# DEVICE2.net
KiCad netlist of a schematic drawn in Altium Designer
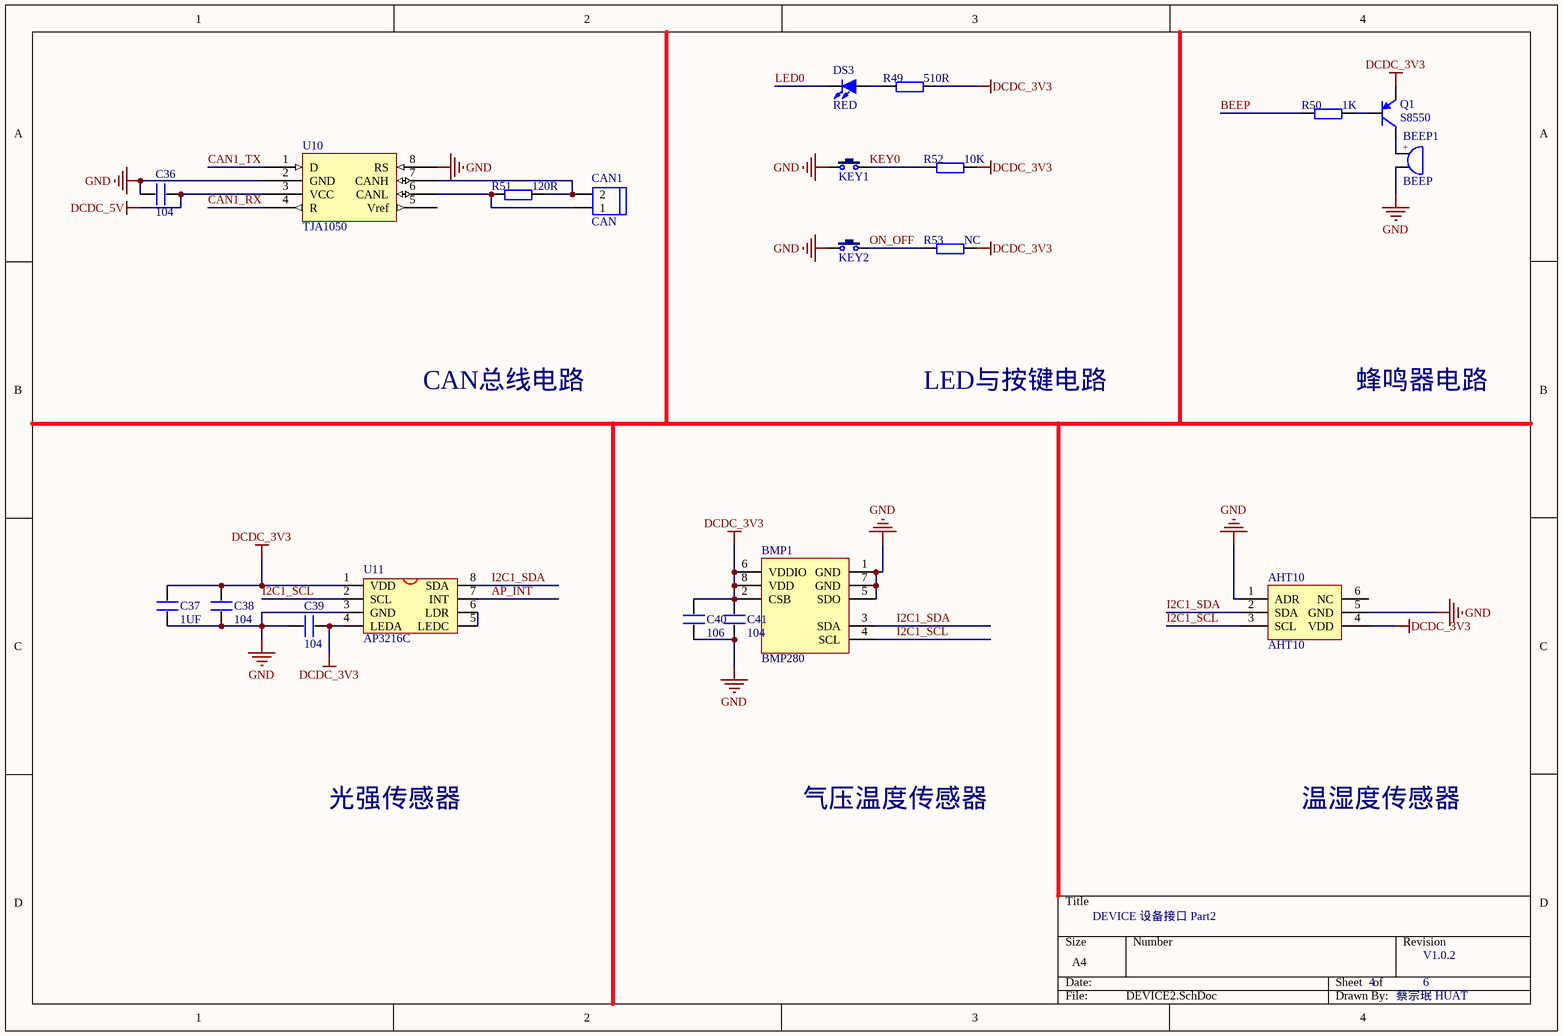
[diagram p0: DEVICE2.SchDoc]

(export (version "E")
  (design (tool "Eeschema 10.0.6"))
  (components
    (comp (ref "AHT10")
      (value "AHT10")
      (footprint "AHT10 温湿度传感器")
      (libsource (lib "ZZW封装汇总") (part "AHT10 温湿度传感器"))
    )
    (comp (ref "BEEP1")
      (value "BEEP")
      (footprint "BEEP 5x9x5.5")
      (description "蜂鸣器")
      (fields (field (name "版权归属") "源创客"))
      (libsource (lib "IMX6UL_ALPHA(底板)_V2.0") (part "BEEP"))
    )
    (comp (ref "BMP1") (value "BMP280") (footprint "BMP280") (libsource (lib "ZZW封装汇总") (part "BMP280")))
    (comp (ref "C36") (value "104") (footprint "C_0603P") (libsource (lib "ZZW封装汇总") (part "C")))
    (comp (ref "C37") (value "1UF") (footprint "C_0603P") (libsource (lib "ZZW封装汇总") (part "C")))
    (comp (ref "C38") (value "104") (footprint "C_0603P") (libsource (lib "ZZW封装汇总") (part "C")))
    (comp (ref "C39") (value "104") (footprint "C_0603P") (libsource (lib "ZZW封装汇总") (part "C")))
    (comp (ref "C40") (value "106") (footprint "C_0603P") (libsource (lib "ZZW封装汇总") (part "C")))
    (comp (ref "C41") (value "104") (footprint "C_0603P") (libsource (lib "ZZW封装汇总") (part "C")))
    (comp (ref "CAN1")
      (value "CAN")
      (footprint "KF301-2P")
      (libsource (lib "IMX6UL_ALPHA(底板)_V2.0") (part "HEAD2"))
    )
    (comp (ref "DS3")
      (value "RED")
      (footprint "LED 0805R")
      (description "贴片LED")
      (fields (field (name "版权归属") "源创客"))
      (libsource (lib "IMX6UL_ALPHA(底板)_V2.0") (part "LED-SMD"))
    )
    (comp (ref "KEY1")
      (value "KEY")
      (footprint "TSW DIP-6*6*5 - 2")
      (description "按键")
      (fields (field (name "版权归属") "源创客"))
      (libsource (lib "IMX6UL_ALPHA(底板)_V2.0") (part "KEY"))
    )
    (comp (ref "KEY2")
      (value "KEY")
      (footprint "TSW DIP-6*6*5 - 2")
      (description "按键")
      (fields (field (name "版权归属") "源创客"))
      (libsource (lib "IMX6UL_ALPHA(底板)_V2.0") (part "KEY"))
    )
    (comp (ref "Q1")
      (value "S8550")
      (footprint "SOT23-3L")
      (description "高频放大-PNP型")
      (fields (field (name "版权归属") "源创客"))
      (libsource (lib "IMX6UL_ALPHA(底板)_V2.0") (part "8550-SMD"))
    )
    (comp (ref "R49") (value "510R") (footprint "R_0603P") (libsource (lib "ZZW封装汇总") (part "R")))
    (comp (ref "R50") (value "1K") (footprint "R_0603P") (libsource (lib "ZZW封装汇总") (part "R")))
    (comp (ref "R51") (value "120R") (footprint "R_0603P") (libsource (lib "ZZW封装汇总") (part "R")))
    (comp (ref "R52") (value "10K") (footprint "R_0603P") (libsource (lib "ZZW封装汇总") (part "R")))
    (comp (ref "R53") (value "NC") (footprint "R_0603P") (libsource (lib "ZZW封装汇总") (part "R")))
    (comp (ref "U10")
      (value "TJA1050")
      (footprint "SOP8_N")
      (libsource (lib "IMX6UL_ALPHA(底板)_V2.0") (part "SN65HVD230D"))
    )
    (comp (ref "U11")
      (value "AP3216C")
      (footprint "QFN8")
      (description "ALS+PS Sensor")
      (libsource (lib "IMX6UL_ALPHA(底板)_V2.0") (part "AP3216C"))
    )
  )
  (nets
    (net (code "1") (name "/AP_INT") (class "Default")
      (node (ref "U11") (pin "7") (pinfunction "INT_7") (pintype "passive"))
    )
    (net (code "2") (name "/BEEP") (class "Default") (node (ref "R50") (pin "1") (pintype "passive")))
    (net (code "3") (name "/CAN1_RX") (class "Default")
      (node (ref "U10") (pin "4") (pinfunction "R_4") (pintype "output"))
    )
    (net (code "4") (name "/CAN1_TX") (class "Default")
      (node (ref "U10") (pin "1") (pinfunction "D_1") (pintype "input"))
    )
    (net (code "5") (name "/I2C1_SCL") (class "Default")
      (node (ref "AHT10") (pin "3") (pinfunction "SCL_3") (pintype "passive"))
      (node (ref "BMP1") (pin "4") (pinfunction "SCL_4") (pintype "passive"))
      (node (ref "U11") (pin "2") (pinfunction "SCL_2") (pintype "passive"))
    )
    (net (code "6") (name "/I2C1_SDA") (class "Default")
      (node (ref "AHT10") (pin "2") (pinfunction "SDA_2") (pintype "passive"))
      (node (ref "BMP1") (pin "3") (pinfunction "SDA_3") (pintype "passive"))
      (node (ref "U11") (pin "8") (pinfunction "SDA_8") (pintype "passive"))
    )
    (net (code "7") (name "/KEY0") (class "Default")
      (node (ref "KEY1") (pin "2") (pinfunction "2_2") (pintype "passive"))
      (node (ref "R52") (pin "1") (pintype "passive"))
    )
    (net (code "8") (name "/LED0") (class "Default")
      (node (ref "DS3") (pin "2") (pinfunction "K_2") (pintype "passive"))
    )
    (net (code "9") (name "/ON_OFF") (class "Default")
      (node (ref "KEY2") (pin "2") (pinfunction "2_2") (pintype "passive"))
      (node (ref "R53") (pin "1") (pintype "passive"))
    )
    (net (code "10") (name "DCDC_3V3") (class "Default")
      (node (ref "AHT10") (pin "4") (pinfunction "VDD_4") (pintype "passive"))
      (node (ref "BMP1") (pin "2") (pinfunction "CSB_2") (pintype "passive"))
      (node (ref "BMP1") (pin "6") (pinfunction "VDDIO_6") (pintype "passive"))
      (node (ref "BMP1") (pin "8") (pinfunction "VDD_8") (pintype "passive"))
      (node (ref "C37") (pin "2") (pintype "passive"))
      (node (ref "C38") (pin "2") (pintype "passive"))
      (node (ref "C39") (pin "2") (pintype "passive"))
      (node (ref "C40") (pin "1") (pintype "passive"))
      (node (ref "C41") (pin "1") (pintype "passive"))
      (node (ref "Q1") (pin "2") (pinfunction "E_2") (pintype "passive"))
      (node (ref "R49") (pin "2") (pintype "passive"))
      (node (ref "R52") (pin "2") (pintype "passive"))
      (node (ref "R53") (pin "2") (pintype "passive"))
      (node (ref "U11") (pin "1") (pinfunction "VDD_1") (pintype "passive"))
      (node (ref "U11") (pin "4") (pinfunction "LEDA_4") (pintype "passive"))
    )
    (net (code "11") (name "DCDC_5V") (class "Default")
      (node (ref "C36") (pin "2") (pintype "passive"))
      (node (ref "U10") (pin "3") (pinfunction "VCC_3") (pintype "power_in"))
    )
    (net (code "12") (name "GND") (class "Default")
      (node (ref "AHT10") (pin "1") (pinfunction "ADR_1") (pintype "passive"))
      (node (ref "AHT10") (pin "5") (pinfunction "GND_5") (pintype "passive"))
      (node (ref "BEEP1") (pin "2") (pinfunction "2_2") (pintype "passive"))
      (node (ref "BMP1") (pin "1") (pinfunction "GND_1") (pintype "passive"))
      (node (ref "BMP1") (pin "5") (pinfunction "SDO_5") (pintype "passive"))
      (node (ref "BMP1") (pin "7") (pinfunction "GND_7") (pintype "passive"))
      (node (ref "C36") (pin "1") (pintype "passive"))
      (node (ref "C37") (pin "1") (pintype "passive"))
      (node (ref "C38") (pin "1") (pintype "passive"))
      (node (ref "C39") (pin "1") (pintype "passive"))
      (node (ref "C40") (pin "2") (pintype "passive"))
      (node (ref "C41") (pin "2") (pintype "passive"))
      (node (ref "KEY1") (pin "1") (pinfunction "1_1") (pintype "passive"))
      (node (ref "KEY2") (pin "1") (pinfunction "1_1") (pintype "passive"))
      (node (ref "U10") (pin "2") (pinfunction "GND_2") (pintype "power_in"))
      (node (ref "U10") (pin "8") (pinfunction "RS_8") (pintype "input"))
      (node (ref "U11") (pin "3") (pinfunction "GND_3") (pintype "passive"))
    )
    (net (code "13") (name "Net-(DS3-A)") (class "Default")
      (node (ref "DS3") (pin "1") (pinfunction "A_1") (pintype "passive"))
      (node (ref "R49") (pin "1") (pintype "passive"))
    )
    (net (code "14") (name "Net-(Q1-B)") (class "Default")
      (node (ref "Q1") (pin "1") (pinfunction "B_1") (pintype "passive"))
      (node (ref "R50") (pin "2") (pintype "passive"))
    )
    (net (code "15") (name "Net-(Q1-C)") (class "Default")
      (node (ref "BEEP1") (pin "1") (pinfunction "1_1") (pintype "passive"))
      (node (ref "Q1") (pin "3") (pinfunction "C_3") (pintype "passive"))
    )
    (net (code "16") (name "Net-(U10-CANH)") (class "Default")
      (node (ref "CAN1") (pin "2") (pinfunction "2_2") (pintype "passive"))
      (node (ref "R51") (pin "2") (pintype "passive"))
      (node (ref "U10") (pin "7") (pinfunction "CANH_7") (pintype "bidirectional"))
    )
    (net (code "17") (name "Net-(U10-CANL)") (class "Default")
      (node (ref "CAN1") (pin "1") (pinfunction "1_1") (pintype "passive"))
      (node (ref "R51") (pin "1") (pintype "passive"))
      (node (ref "U10") (pin "6") (pinfunction "CANL_6") (pintype "bidirectional"))
    )
    (net (code "18") (name "Net-(U11-LDR)") (class "Default")
      (node (ref "U11") (pin "5") (pinfunction "LEDC_5") (pintype "passive"))
      (node (ref "U11") (pin "6") (pinfunction "LDR_6") (pintype "passive"))
    )
    (net (code "19") (name "unconnected-(AHT10-NC-Pad6)") (class "Default")
      (node (ref "AHT10") (pin "6") (pinfunction "NC_6") (pintype "passive"))
    )
    (net (code "20") (name "unconnected-(U10-Vref-Pad5)") (class "Default")
      (node (ref "U10") (pin "5") (pinfunction "Vref_5") (pintype "output"))
    )
  )
)
